# motor_shield__SD_v2_0.net
KiCad netlist of a schematic drawn in EAGLE
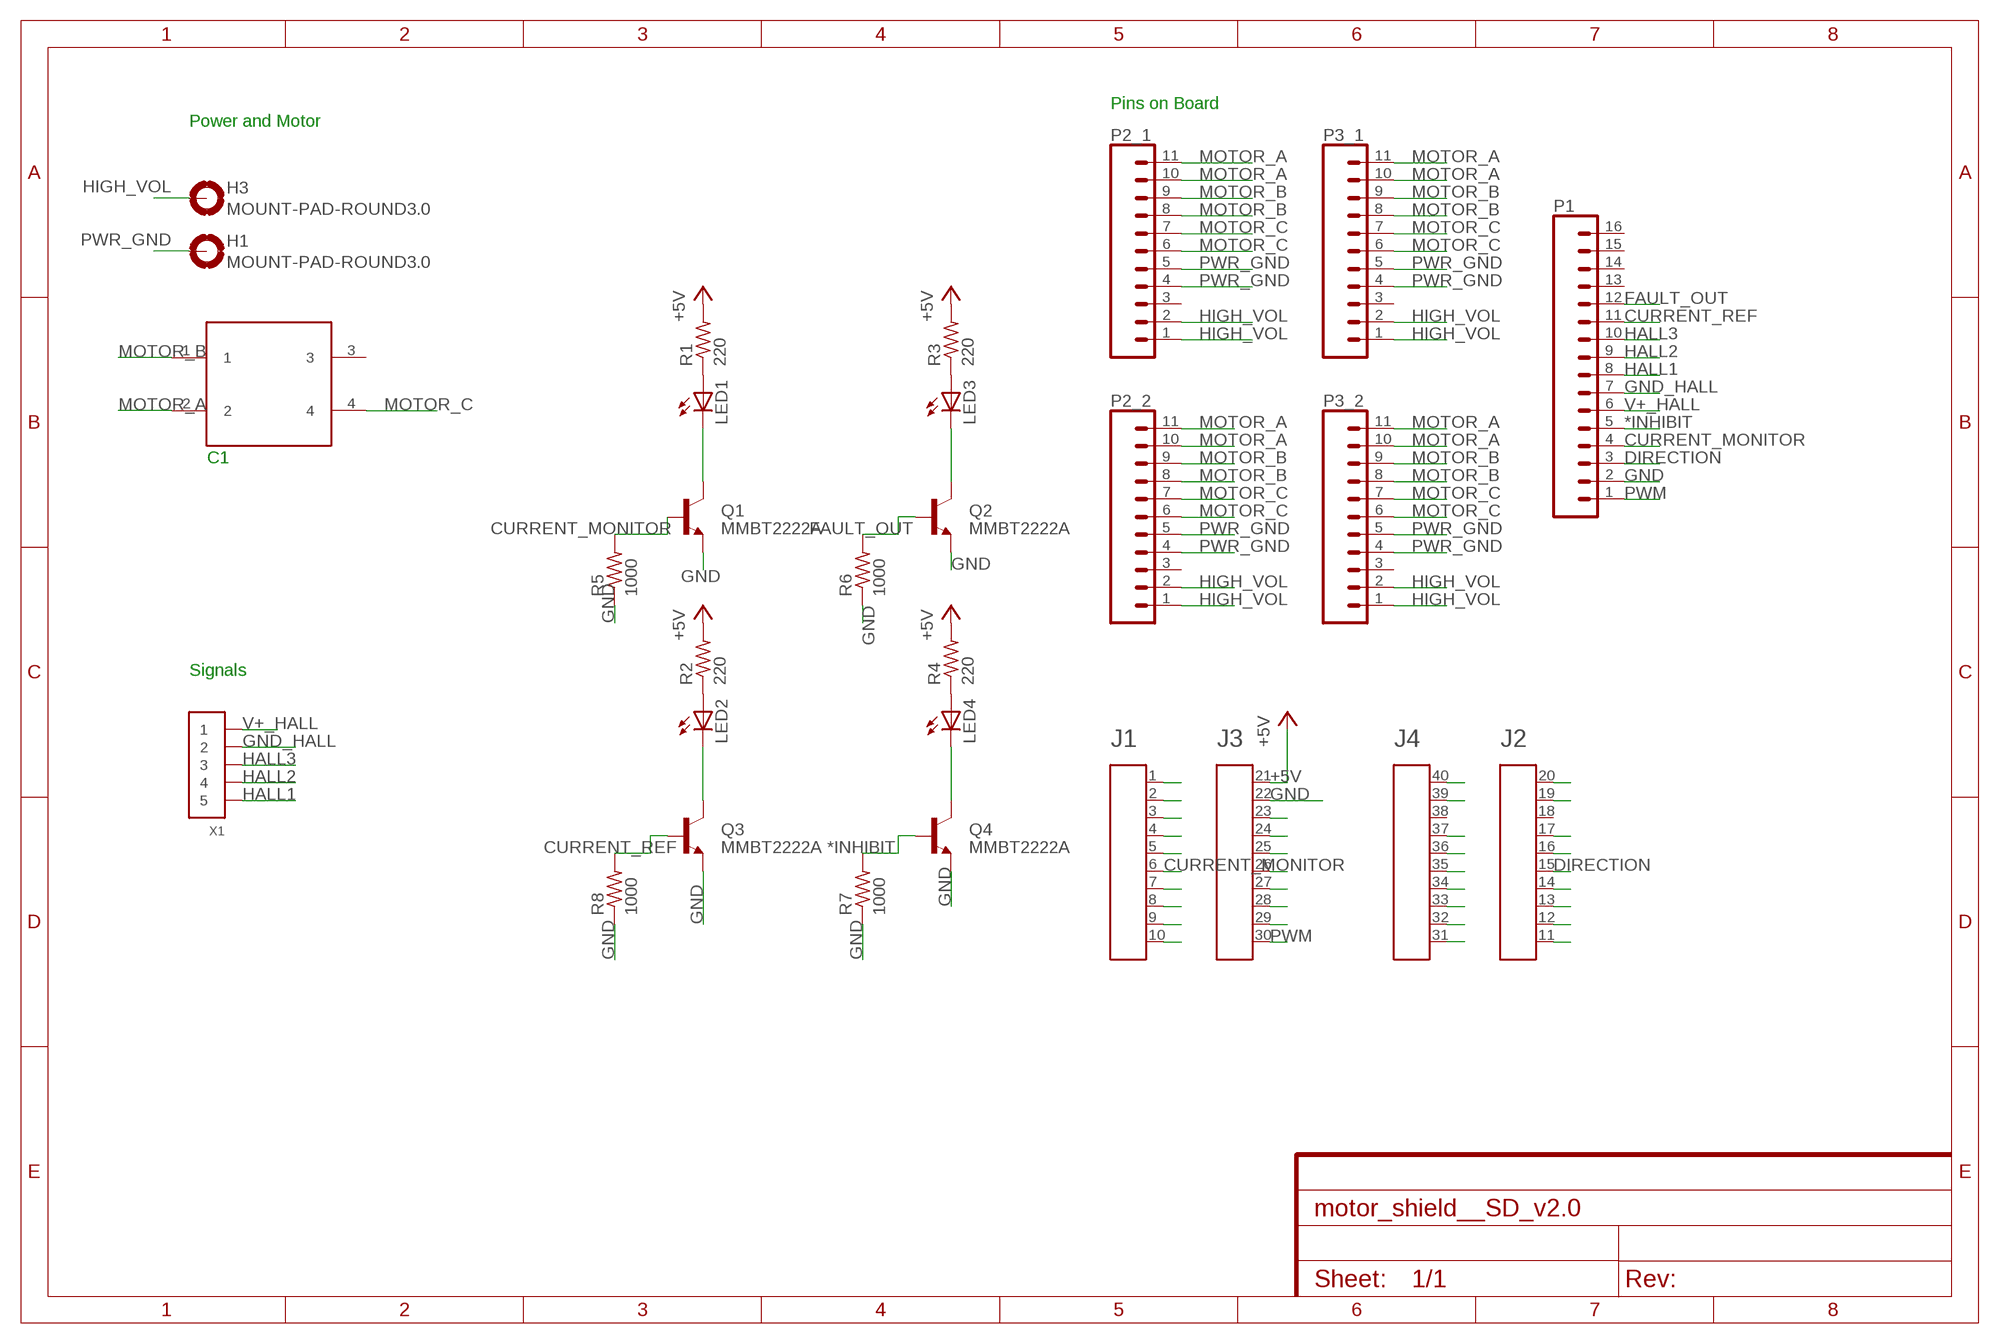
[diagram p0: schematic, sheet 1]

(export (version "E")
  (design (tool "Eeschema 10.0.6"))
  (components
    (comp (ref "A1")
      (value "HEADER4X10-BOOSTERPACK")
      (footprint "eagle-import:4X10-BOOSTERPACK")
      (libsource (lib "eagle-import") (part "HEADER4X10-BOOSTERPACK"))
    )
    (comp (ref "C1")
      (value "MOLEX4CON")
      (footprint "eagle-import:MOLEX4CON")
      (libsource (lib "eagle-import") (part "MOLEX4CON"))
    )
    (comp (ref "H1")
      (value "MOUNT-PAD-ROUND3.0")
      (footprint "eagle-import:3,0-PAD")
      (libsource (lib "eagle-import") (part "MOUNT-PAD-ROUND3.0"))
    )
    (comp (ref "H3")
      (value "MOUNT-PAD-ROUND3.0")
      (footprint "eagle-import:3,0-PAD")
      (libsource (lib "eagle-import") (part "MOUNT-PAD-ROUND3.0"))
    )
    (comp (ref "LED1")
      (value "LEDCHIPLED_0805")
      (footprint "eagle-import:CHIPLED_0805")
      (libsource (lib "eagle-import") (part "LEDCHIPLED_0805"))
    )
    (comp (ref "LED2")
      (value "LEDCHIPLED_0805")
      (footprint "eagle-import:CHIPLED_0805")
      (libsource (lib "eagle-import") (part "LEDCHIPLED_0805"))
    )
    (comp (ref "LED3")
      (value "LEDCHIPLED_0805")
      (footprint "eagle-import:CHIPLED_0805")
      (libsource (lib "eagle-import") (part "LEDCHIPLED_0805"))
    )
    (comp (ref "LED4")
      (value "LEDCHIPLED_0805")
      (footprint "eagle-import:CHIPLED_0805")
      (libsource (lib "eagle-import") (part "LEDCHIPLED_0805"))
    )
    (comp (ref "P1")
      (value "CONN_16LOCK")
      (footprint "eagle-import:1X16_LOCK")
      (libsource (lib "eagle-import") (part "CONN_16LOCK"))
    )
    (comp (ref "P2_1")
      (value "CONN_11")
      (footprint "eagle-import:1X11")
      (libsource (lib "eagle-import") (part "CONN_11"))
    )
    (comp (ref "P2_2")
      (value "CONN_11")
      (footprint "eagle-import:1X11")
      (libsource (lib "eagle-import") (part "CONN_11"))
    )
    (comp (ref "P3_1")
      (value "CONN_11")
      (footprint "eagle-import:1X11")
      (libsource (lib "eagle-import") (part "CONN_11"))
    )
    (comp (ref "P3_2")
      (value "CONN_11")
      (footprint "eagle-import:1X11")
      (libsource (lib "eagle-import") (part "CONN_11"))
    )
    (comp (ref "Q1")
      (value "MMBT2222A")
      (footprint "eagle-import:SOT23-3")
      (libsource (lib "eagle-import") (part "TRANSISTOR_NPNMMBT2222A"))
    )
    (comp (ref "Q2")
      (value "MMBT2222A")
      (footprint "eagle-import:SOT23-3")
      (libsource (lib "eagle-import") (part "TRANSISTOR_NPNMMBT2222A"))
    )
    (comp (ref "Q3")
      (value "MMBT2222A")
      (footprint "eagle-import:SOT23-3")
      (libsource (lib "eagle-import") (part "TRANSISTOR_NPNMMBT2222A"))
    )
    (comp (ref "Q4")
      (value "MMBT2222A")
      (footprint "eagle-import:SOT23-3")
      (libsource (lib "eagle-import") (part "TRANSISTOR_NPNMMBT2222A"))
    )
    (comp (ref "R1")
      (value "220")
      (footprint "eagle-import:R0603")
      (libsource (lib "eagle-import") (part "R-US_R0603"))
    )
    (comp (ref "R2")
      (value "220")
      (footprint "eagle-import:R0603")
      (libsource (lib "eagle-import") (part "R-US_R0603"))
    )
    (comp (ref "R3")
      (value "220")
      (footprint "eagle-import:R0603")
      (libsource (lib "eagle-import") (part "R-US_R0603"))
    )
    (comp (ref "R4")
      (value "220")
      (footprint "eagle-import:R0603")
      (libsource (lib "eagle-import") (part "R-US_R0603"))
    )
    (comp (ref "R5")
      (value "1000")
      (footprint "eagle-import:R0603")
      (libsource (lib "eagle-import") (part "R-US_R0603"))
    )
    (comp (ref "R6")
      (value "1000")
      (footprint "eagle-import:R0603")
      (libsource (lib "eagle-import") (part "R-US_R0603"))
    )
    (comp (ref "R7")
      (value "1000")
      (footprint "eagle-import:R0603")
      (libsource (lib "eagle-import") (part "R-US_R0603"))
    )
    (comp (ref "R8")
      (value "1000")
      (footprint "eagle-import:R0603")
      (libsource (lib "eagle-import") (part "R-US_R0603"))
    )
    (comp (ref "X1")
      (value "CONN_5-1-53261")
      (footprint "eagle-import:PB-53261-05")
      (libsource (lib "eagle-import") (part "CONN_5-1-53261"))
    )
  )
  (nets
    (net (code "1") (name "+5V") (class "Default")
      (node (ref "A1") (pin "21") (pinfunction "P$21_21") (pintype "bidirectional"))
      (node (ref "R1") (pin "2") (pinfunction "2_2") (pintype "passive"))
      (node (ref "R2") (pin "2") (pinfunction "2_2") (pintype "passive"))
      (node (ref "R3") (pin "2") (pinfunction "2_2") (pintype "passive"))
      (node (ref "R4") (pin "2") (pinfunction "2_2") (pintype "passive"))
    )
    (net (code "2") (name "/*INHIBIT") (class "Default")
      (node (ref "P1") (pin "5") (pinfunction "5_5") (pintype "passive"))
      (node (ref "Q4") (pin "1") (pinfunction "B_1") (pintype "passive"))
      (node (ref "R7") (pin "2") (pinfunction "2_2") (pintype "passive"))
    )
    (net (code "3") (name "/CURRENT_MONITOR") (class "Default")
      (node (ref "A1") (pin "6") (pinfunction "P$6_6") (pintype "bidirectional"))
      (node (ref "P1") (pin "4") (pinfunction "4_4") (pintype "passive"))
      (node (ref "Q1") (pin "1") (pinfunction "B_1") (pintype "passive"))
      (node (ref "R5") (pin "2") (pinfunction "2_2") (pintype "passive"))
    )
    (net (code "4") (name "/CURRENT_REF") (class "Default")
      (node (ref "P1") (pin "11") (pinfunction "11_11") (pintype "passive"))
      (node (ref "Q3") (pin "1") (pinfunction "B_1") (pintype "passive"))
      (node (ref "R8") (pin "2") (pinfunction "2_2") (pintype "passive"))
    )
    (net (code "5") (name "/DIRECTION") (class "Default")
      (node (ref "A1") (pin "15") (pinfunction "P$15_15") (pintype "bidirectional"))
      (node (ref "P1") (pin "3") (pinfunction "3_3") (pintype "passive"))
    )
    (net (code "6") (name "/FAULT_OUT") (class "Default")
      (node (ref "P1") (pin "12") (pinfunction "12_12") (pintype "passive"))
      (node (ref "Q2") (pin "1") (pinfunction "B_1") (pintype "passive"))
      (node (ref "R6") (pin "2") (pinfunction "2_2") (pintype "passive"))
    )
    (net (code "7") (name "/GND") (class "Default")
      (node (ref "A1") (pin "22") (pinfunction "P$22_22") (pintype "bidirectional"))
      (node (ref "P1") (pin "2") (pinfunction "2_2") (pintype "passive"))
      (node (ref "Q1") (pin "2") (pinfunction "E_2") (pintype "passive"))
      (node (ref "Q2") (pin "2") (pinfunction "E_2") (pintype "passive"))
      (node (ref "Q3") (pin "2") (pinfunction "E_2") (pintype "passive"))
      (node (ref "Q4") (pin "2") (pinfunction "E_2") (pintype "passive"))
      (node (ref "R5") (pin "1") (pinfunction "1_1") (pintype "passive"))
      (node (ref "R6") (pin "1") (pinfunction "1_1") (pintype "passive"))
      (node (ref "R7") (pin "1") (pinfunction "1_1") (pintype "passive"))
      (node (ref "R8") (pin "1") (pinfunction "1_1") (pintype "passive"))
    )
    (net (code "8") (name "/GND_HALL") (class "Default")
      (node (ref "P1") (pin "7") (pinfunction "7_7") (pintype "passive"))
      (node (ref "X1") (pin "2") (pinfunction "2_2") (pintype "bidirectional"))
    )
    (net (code "9") (name "/HALL1") (class "Default")
      (node (ref "P1") (pin "8") (pinfunction "8_8") (pintype "passive"))
      (node (ref "X1") (pin "5") (pinfunction "5_5") (pintype "bidirectional"))
    )
    (net (code "10") (name "/HALL2") (class "Default")
      (node (ref "P1") (pin "9") (pinfunction "9_9") (pintype "passive"))
      (node (ref "X1") (pin "4") (pinfunction "4_4") (pintype "bidirectional"))
    )
    (net (code "11") (name "/HALL3") (class "Default")
      (node (ref "P1") (pin "10") (pinfunction "10_10") (pintype "passive"))
      (node (ref "X1") (pin "3") (pinfunction "3_3") (pintype "bidirectional"))
    )
    (net (code "12") (name "/HIGH_VOL") (class "Default")
      (node (ref "H3") (pin "B3,0") (pinfunction "MOUNT_B3,0") (pintype "passive"))
      (node (ref "P2_1") (pin "1") (pinfunction "1_1") (pintype "passive"))
      (node (ref "P2_1") (pin "2") (pinfunction "2_2") (pintype "passive"))
      (node (ref "P2_2") (pin "1") (pinfunction "1_1") (pintype "passive"))
      (node (ref "P2_2") (pin "2") (pinfunction "2_2") (pintype "passive"))
      (node (ref "P3_1") (pin "1") (pinfunction "1_1") (pintype "passive"))
      (node (ref "P3_1") (pin "2") (pinfunction "2_2") (pintype "passive"))
      (node (ref "P3_2") (pin "1") (pinfunction "1_1") (pintype "passive"))
      (node (ref "P3_2") (pin "2") (pinfunction "2_2") (pintype "passive"))
    )
    (net (code "13") (name "/MOTOR_A") (class "Default")
      (node (ref "C1") (pin "2") (pinfunction "2_2") (pintype "bidirectional"))
      (node (ref "P2_1") (pin "10") (pinfunction "10_10") (pintype "passive"))
      (node (ref "P2_1") (pin "11") (pinfunction "11_11") (pintype "passive"))
      (node (ref "P2_2") (pin "10") (pinfunction "10_10") (pintype "passive"))
      (node (ref "P2_2") (pin "11") (pinfunction "11_11") (pintype "passive"))
      (node (ref "P3_1") (pin "10") (pinfunction "10_10") (pintype "passive"))
      (node (ref "P3_1") (pin "11") (pinfunction "11_11") (pintype "passive"))
      (node (ref "P3_2") (pin "10") (pinfunction "10_10") (pintype "passive"))
      (node (ref "P3_2") (pin "11") (pinfunction "11_11") (pintype "passive"))
    )
    (net (code "14") (name "/MOTOR_B") (class "Default")
      (node (ref "C1") (pin "1") (pinfunction "1_1") (pintype "bidirectional"))
      (node (ref "P2_1") (pin "8") (pinfunction "8_8") (pintype "passive"))
      (node (ref "P2_1") (pin "9") (pinfunction "9_9") (pintype "passive"))
      (node (ref "P2_2") (pin "8") (pinfunction "8_8") (pintype "passive"))
      (node (ref "P2_2") (pin "9") (pinfunction "9_9") (pintype "passive"))
      (node (ref "P3_1") (pin "8") (pinfunction "8_8") (pintype "passive"))
      (node (ref "P3_1") (pin "9") (pinfunction "9_9") (pintype "passive"))
      (node (ref "P3_2") (pin "8") (pinfunction "8_8") (pintype "passive"))
      (node (ref "P3_2") (pin "9") (pinfunction "9_9") (pintype "passive"))
    )
    (net (code "15") (name "/MOTOR_C") (class "Default")
      (node (ref "C1") (pin "4") (pinfunction "4_4") (pintype "bidirectional"))
      (node (ref "P2_1") (pin "6") (pinfunction "6_6") (pintype "passive"))
      (node (ref "P2_1") (pin "7") (pinfunction "7_7") (pintype "passive"))
      (node (ref "P2_2") (pin "6") (pinfunction "6_6") (pintype "passive"))
      (node (ref "P2_2") (pin "7") (pinfunction "7_7") (pintype "passive"))
      (node (ref "P3_1") (pin "6") (pinfunction "6_6") (pintype "passive"))
      (node (ref "P3_1") (pin "7") (pinfunction "7_7") (pintype "passive"))
      (node (ref "P3_2") (pin "6") (pinfunction "6_6") (pintype "passive"))
      (node (ref "P3_2") (pin "7") (pinfunction "7_7") (pintype "passive"))
    )
    (net (code "16") (name "/PWM") (class "Default")
      (node (ref "A1") (pin "30") (pinfunction "P$30_30") (pintype "bidirectional"))
      (node (ref "P1") (pin "1") (pinfunction "1_1") (pintype "passive"))
    )
    (net (code "17") (name "/PWR_GND") (class "Default")
      (node (ref "H1") (pin "B3,0") (pinfunction "MOUNT_B3,0") (pintype "passive"))
      (node (ref "P2_1") (pin "4") (pinfunction "4_4") (pintype "passive"))
      (node (ref "P2_1") (pin "5") (pinfunction "5_5") (pintype "passive"))
      (node (ref "P2_2") (pin "4") (pinfunction "4_4") (pintype "passive"))
      (node (ref "P2_2") (pin "5") (pinfunction "5_5") (pintype "passive"))
      (node (ref "P3_1") (pin "4") (pinfunction "4_4") (pintype "passive"))
      (node (ref "P3_1") (pin "5") (pinfunction "5_5") (pintype "passive"))
      (node (ref "P3_2") (pin "4") (pinfunction "4_4") (pintype "passive"))
      (node (ref "P3_2") (pin "5") (pinfunction "5_5") (pintype "passive"))
    )
    (net (code "18") (name "/V+_HALL") (class "Default")
      (node (ref "P1") (pin "6") (pinfunction "6_6") (pintype "passive"))
      (node (ref "X1") (pin "1") (pinfunction "1_1") (pintype "bidirectional"))
    )
    (net (code "19") (name "Net-(LED1-PadA)") (class "Default")
      (node (ref "LED1") (pin "A") (pinfunction "A_A") (pintype "passive"))
      (node (ref "R1") (pin "1") (pinfunction "1_1") (pintype "passive"))
    )
    (net (code "20") (name "Net-(LED2-PadA)") (class "Default")
      (node (ref "LED2") (pin "A") (pinfunction "A_A") (pintype "passive"))
      (node (ref "R2") (pin "1") (pinfunction "1_1") (pintype "passive"))
    )
    (net (code "21") (name "Net-(LED3-PadA)") (class "Default")
      (node (ref "LED3") (pin "A") (pinfunction "A_A") (pintype "passive"))
      (node (ref "R3") (pin "1") (pinfunction "1_1") (pintype "passive"))
    )
    (net (code "22") (name "Net-(LED4-PadA)") (class "Default")
      (node (ref "LED4") (pin "A") (pinfunction "A_A") (pintype "passive"))
      (node (ref "R4") (pin "1") (pinfunction "1_1") (pintype "passive"))
    )
    (net (code "23") (name "Net-(Q1-C)") (class "Default")
      (node (ref "LED1") (pin "C") (pinfunction "C_C") (pintype "passive"))
      (node (ref "Q1") (pin "3") (pinfunction "C_3") (pintype "passive"))
    )
    (net (code "24") (name "Net-(Q2-C)") (class "Default")
      (node (ref "LED3") (pin "C") (pinfunction "C_C") (pintype "passive"))
      (node (ref "Q2") (pin "3") (pinfunction "C_3") (pintype "passive"))
    )
    (net (code "25") (name "Net-(Q3-C)") (class "Default")
      (node (ref "LED2") (pin "C") (pinfunction "C_C") (pintype "passive"))
      (node (ref "Q3") (pin "3") (pinfunction "C_3") (pintype "passive"))
    )
    (net (code "26") (name "Net-(Q4-C)") (class "Default")
      (node (ref "LED4") (pin "C") (pinfunction "C_C") (pintype "passive"))
      (node (ref "Q4") (pin "3") (pinfunction "C_3") (pintype "passive"))
    )
    (net (code "27") (name "unconnected-(A1-P$1-Pad1)") (class "Default")
      (node (ref "A1") (pin "1") (pinfunction "P$1_1") (pintype "bidirectional"))
    )
    (net (code "28") (name "unconnected-(A1-P$2-Pad2)") (class "Default")
      (node (ref "A1") (pin "2") (pinfunction "P$2_2") (pintype "bidirectional"))
    )
    (net (code "29") (name "unconnected-(A1-P$3-Pad3)") (class "Default")
      (node (ref "A1") (pin "3") (pinfunction "P$3_3") (pintype "bidirectional"))
    )
    (net (code "30") (name "unconnected-(A1-P$4-Pad4)") (class "Default")
      (node (ref "A1") (pin "4") (pinfunction "P$4_4") (pintype "bidirectional"))
    )
    (net (code "31") (name "unconnected-(A1-P$5-Pad5)") (class "Default")
      (node (ref "A1") (pin "5") (pinfunction "P$5_5") (pintype "bidirectional"))
    )
    (net (code "32") (name "unconnected-(A1-P$7-Pad7)") (class "Default")
      (node (ref "A1") (pin "7") (pinfunction "P$7_7") (pintype "bidirectional"))
    )
    (net (code "33") (name "unconnected-(A1-P$8-Pad8)") (class "Default")
      (node (ref "A1") (pin "8") (pinfunction "P$8_8") (pintype "bidirectional"))
    )
    (net (code "34") (name "unconnected-(A1-P$9-Pad9)") (class "Default")
      (node (ref "A1") (pin "9") (pinfunction "P$9_9") (pintype "bidirectional"))
    )
    (net (code "35") (name "unconnected-(A1-P$10-Pad10)") (class "Default")
      (node (ref "A1") (pin "10") (pinfunction "P$10_10") (pintype "bidirectional"))
    )
    (net (code "36") (name "unconnected-(A1-P$11-Pad11)") (class "Default")
      (node (ref "A1") (pin "11") (pinfunction "P$11_11") (pintype "bidirectional"))
    )
    (net (code "37") (name "unconnected-(A1-P$12-Pad12)") (class "Default")
      (node (ref "A1") (pin "12") (pinfunction "P$12_12") (pintype "bidirectional"))
    )
    (net (code "38") (name "unconnected-(A1-P$13-Pad13)") (class "Default")
      (node (ref "A1") (pin "13") (pinfunction "P$13_13") (pintype "bidirectional"))
    )
    (net (code "39") (name "unconnected-(A1-P$14-Pad14)") (class "Default")
      (node (ref "A1") (pin "14") (pinfunction "P$14_14") (pintype "bidirectional"))
    )
    (net (code "40") (name "unconnected-(A1-P$16-Pad16)") (class "Default")
      (node (ref "A1") (pin "16") (pinfunction "P$16_16") (pintype "bidirectional"))
    )
    (net (code "41") (name "unconnected-(A1-P$17-Pad17)") (class "Default")
      (node (ref "A1") (pin "17") (pinfunction "P$17_17") (pintype "bidirectional"))
    )
    (net (code "42") (name "unconnected-(A1-P$18-Pad18)") (class "Default")
      (node (ref "A1") (pin "18") (pinfunction "P$18_18") (pintype "bidirectional"))
    )
    (net (code "43") (name "unconnected-(A1-P$19-Pad19)") (class "Default")
      (node (ref "A1") (pin "19") (pinfunction "P$19_19") (pintype "bidirectional"))
    )
    (net (code "44") (name "unconnected-(A1-P$20-Pad20)") (class "Default")
      (node (ref "A1") (pin "20") (pinfunction "P$20_20") (pintype "bidirectional"))
    )
    (net (code "45") (name "unconnected-(A1-P$23-Pad23)") (class "Default")
      (node (ref "A1") (pin "23") (pinfunction "P$23_23") (pintype "bidirectional"))
    )
    (net (code "46") (name "unconnected-(A1-P$24-Pad24)") (class "Default")
      (node (ref "A1") (pin "24") (pinfunction "P$24_24") (pintype "bidirectional"))
    )
    (net (code "47") (name "unconnected-(A1-P$25-Pad25)") (class "Default")
      (node (ref "A1") (pin "25") (pinfunction "P$25_25") (pintype "bidirectional"))
    )
    (net (code "48") (name "unconnected-(A1-P$26-Pad26)") (class "Default")
      (node (ref "A1") (pin "26") (pinfunction "P$26_26") (pintype "bidirectional"))
    )
    (net (code "49") (name "unconnected-(A1-P$27-Pad27)") (class "Default")
      (node (ref "A1") (pin "27") (pinfunction "P$27_27") (pintype "bidirectional"))
    )
    (net (code "50") (name "unconnected-(A1-P$28-Pad28)") (class "Default")
      (node (ref "A1") (pin "28") (pinfunction "P$28_28") (pintype "bidirectional"))
    )
    (net (code "51") (name "unconnected-(A1-P$29-Pad29)") (class "Default")
      (node (ref "A1") (pin "29") (pinfunction "P$29_29") (pintype "bidirectional"))
    )
    (net (code "52") (name "unconnected-(A1-P$31-Pad31)") (class "Default")
      (node (ref "A1") (pin "31") (pinfunction "P$31_31") (pintype "bidirectional"))
    )
    (net (code "53") (name "unconnected-(A1-P$32-Pad32)") (class "Default")
      (node (ref "A1") (pin "32") (pinfunction "P$32_32") (pintype "bidirectional"))
    )
    (net (code "54") (name "unconnected-(A1-P$33-Pad33)") (class "Default")
      (node (ref "A1") (pin "33") (pinfunction "P$33_33") (pintype "bidirectional"))
    )
    (net (code "55") (name "unconnected-(A1-P$34-Pad34)") (class "Default")
      (node (ref "A1") (pin "34") (pinfunction "P$34_34") (pintype "bidirectional"))
    )
    (net (code "56") (name "unconnected-(A1-P$35-Pad35)") (class "Default")
      (node (ref "A1") (pin "35") (pinfunction "P$35_35") (pintype "bidirectional"))
    )
    (net (code "57") (name "unconnected-(A1-P$36-Pad36)") (class "Default")
      (node (ref "A1") (pin "36") (pinfunction "P$36_36") (pintype "bidirectional"))
    )
    (net (code "58") (name "unconnected-(A1-P$37-Pad37)") (class "Default")
      (node (ref "A1") (pin "37") (pinfunction "P$37_37") (pintype "bidirectional"))
    )
    (net (code "59") (name "unconnected-(A1-P$38-Pad38)") (class "Default")
      (node (ref "A1") (pin "38") (pinfunction "P$38_38") (pintype "bidirectional"))
    )
    (net (code "60") (name "unconnected-(A1-P$39-Pad39)") (class "Default")
      (node (ref "A1") (pin "39") (pinfunction "P$39_39") (pintype "bidirectional"))
    )
    (net (code "61") (name "unconnected-(A1-P$40-Pad40)") (class "Default")
      (node (ref "A1") (pin "40") (pinfunction "P$40_40") (pintype "bidirectional"))
    )
    (net (code "62") (name "unconnected-(C1-Pad3)") (class "Default")
      (node (ref "C1") (pin "3") (pinfunction "3_3") (pintype "bidirectional"))
    )
    (net (code "63") (name "unconnected-(P1-Pad13)") (class "Default")
      (node (ref "P1") (pin "13") (pinfunction "13_13") (pintype "passive"))
    )
    (net (code "64") (name "unconnected-(P1-Pad14)") (class "Default")
      (node (ref "P1") (pin "14") (pinfunction "14_14") (pintype "passive"))
    )
    (net (code "65") (name "unconnected-(P1-Pad15)") (class "Default")
      (node (ref "P1") (pin "15") (pinfunction "15_15") (pintype "passive"))
    )
    (net (code "66") (name "unconnected-(P1-Pad16)") (class "Default")
      (node (ref "P1") (pin "16") (pinfunction "16_16") (pintype "passive"))
    )
    (net (code "67") (name "unconnected-(P2_1-Pad3)") (class "Default")
      (node (ref "P2_1") (pin "3") (pinfunction "3_3") (pintype "passive"))
    )
    (net (code "68") (name "unconnected-(P2_2-Pad3)") (class "Default")
      (node (ref "P2_2") (pin "3") (pinfunction "3_3") (pintype "passive"))
    )
    (net (code "69") (name "unconnected-(P3_1-Pad3)") (class "Default")
      (node (ref "P3_1") (pin "3") (pinfunction "3_3") (pintype "passive"))
    )
    (net (code "70") (name "unconnected-(P3_2-Pad3)") (class "Default")
      (node (ref "P3_2") (pin "3") (pinfunction "3_3") (pintype "passive"))
    )
  )
)
